# 2_Microcontroler_48.net
KiCad netlist of a schematic drawn in Altium Designer
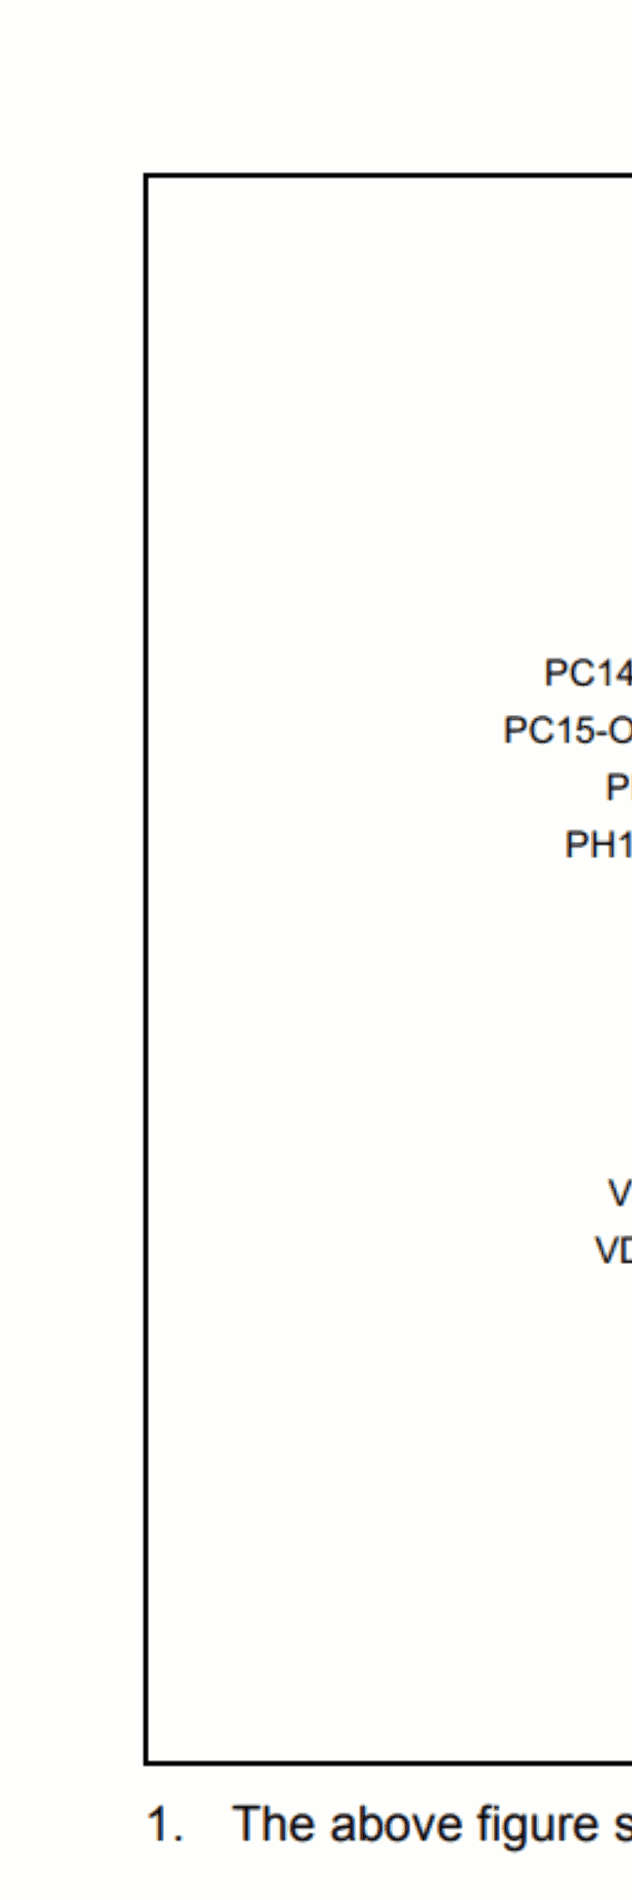
[diagram p0: 2_Microcontroler_48.SchDoc, top left]
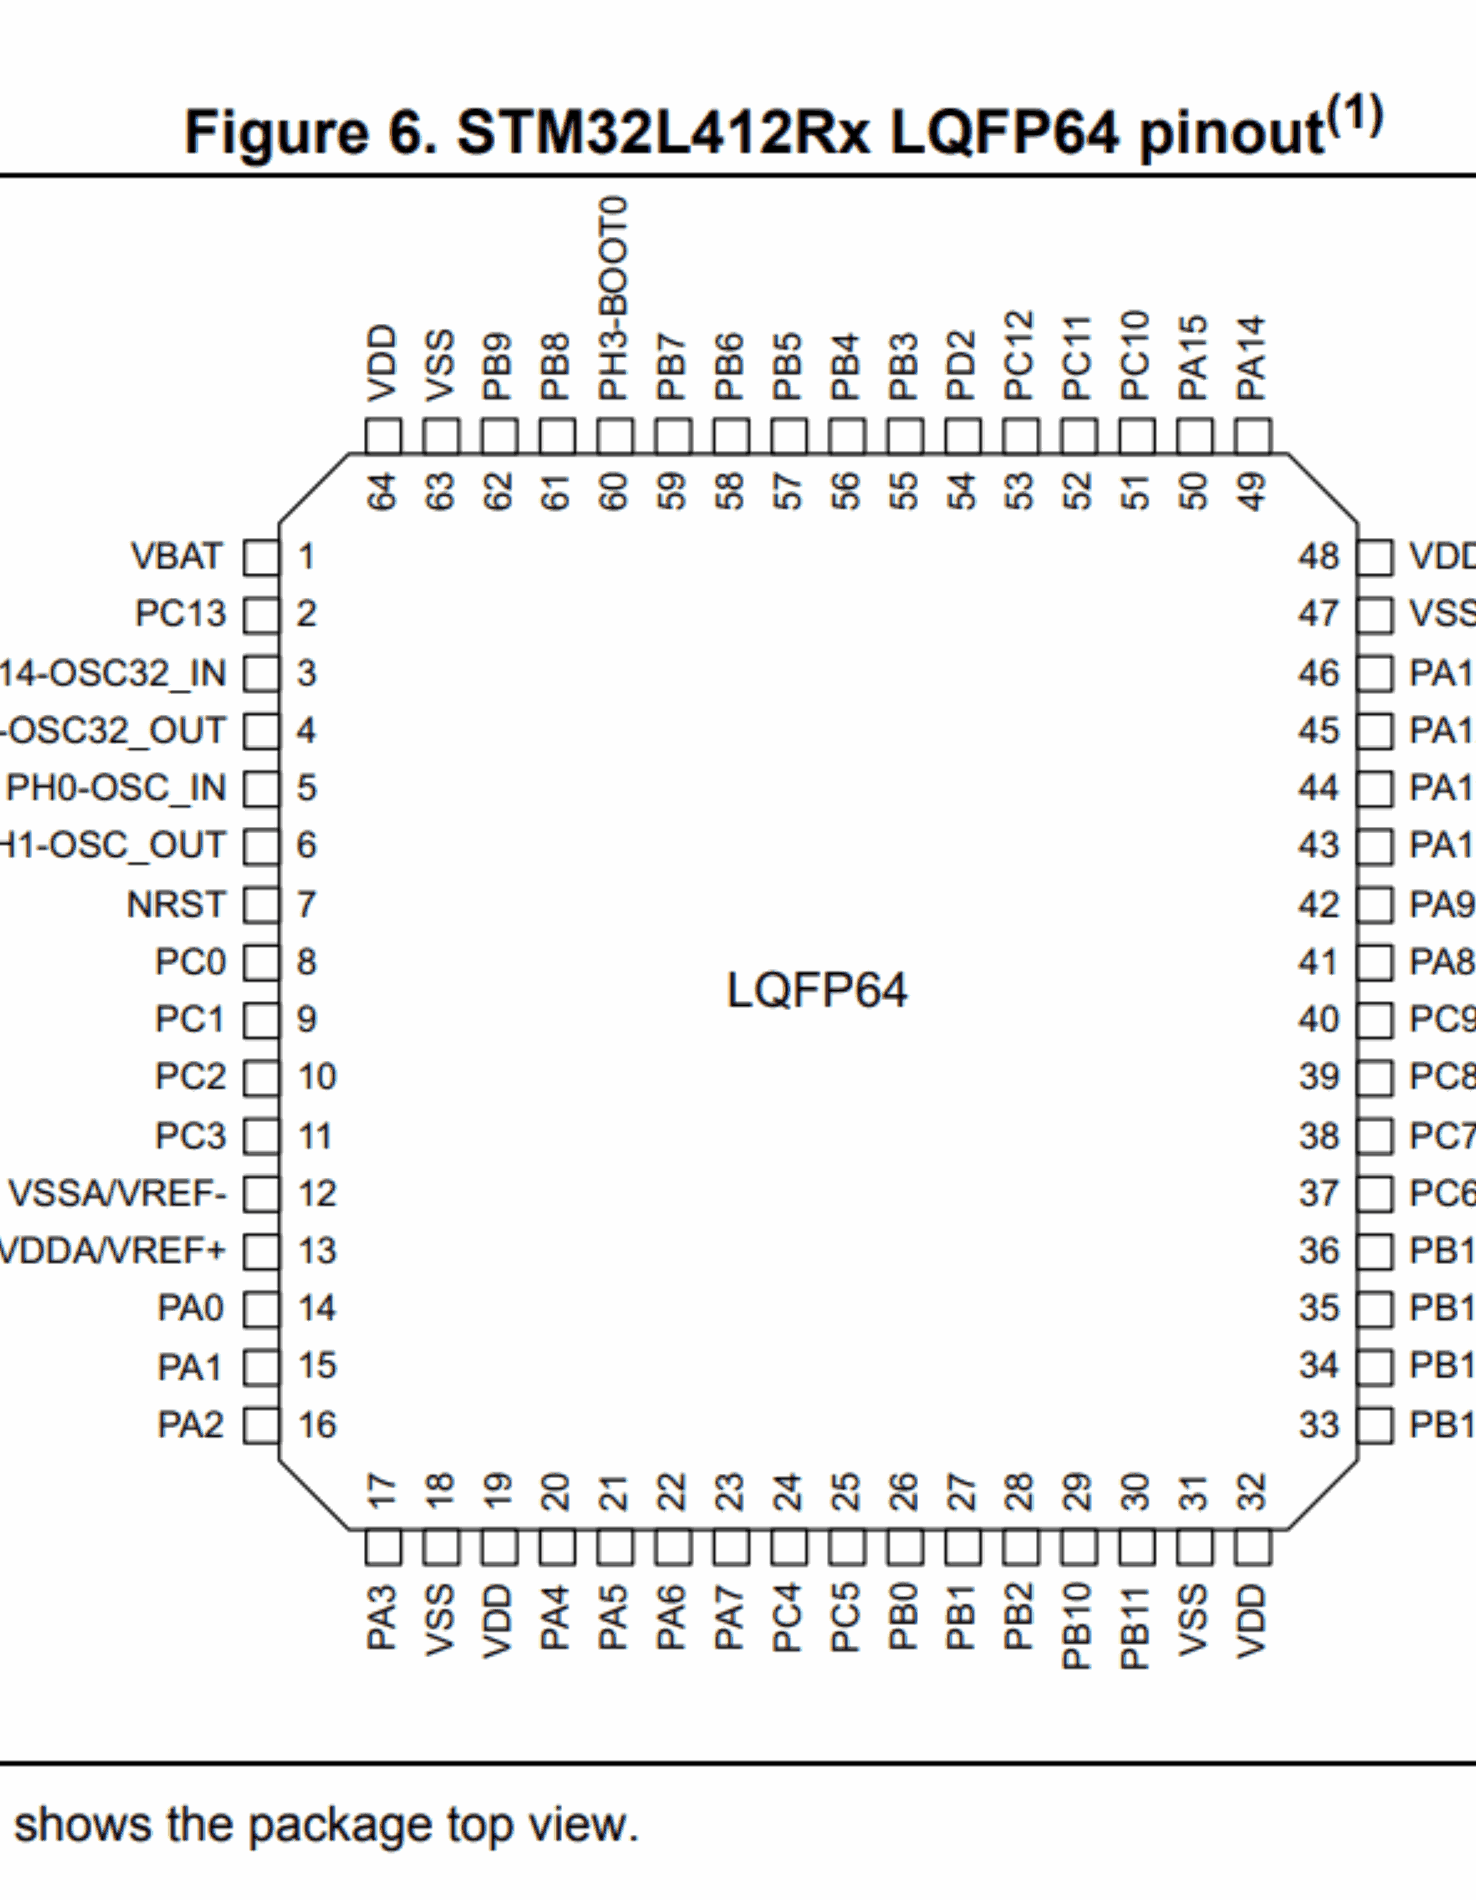
[diagram p1: 2_Microcontroler_48.SchDoc, top middle]
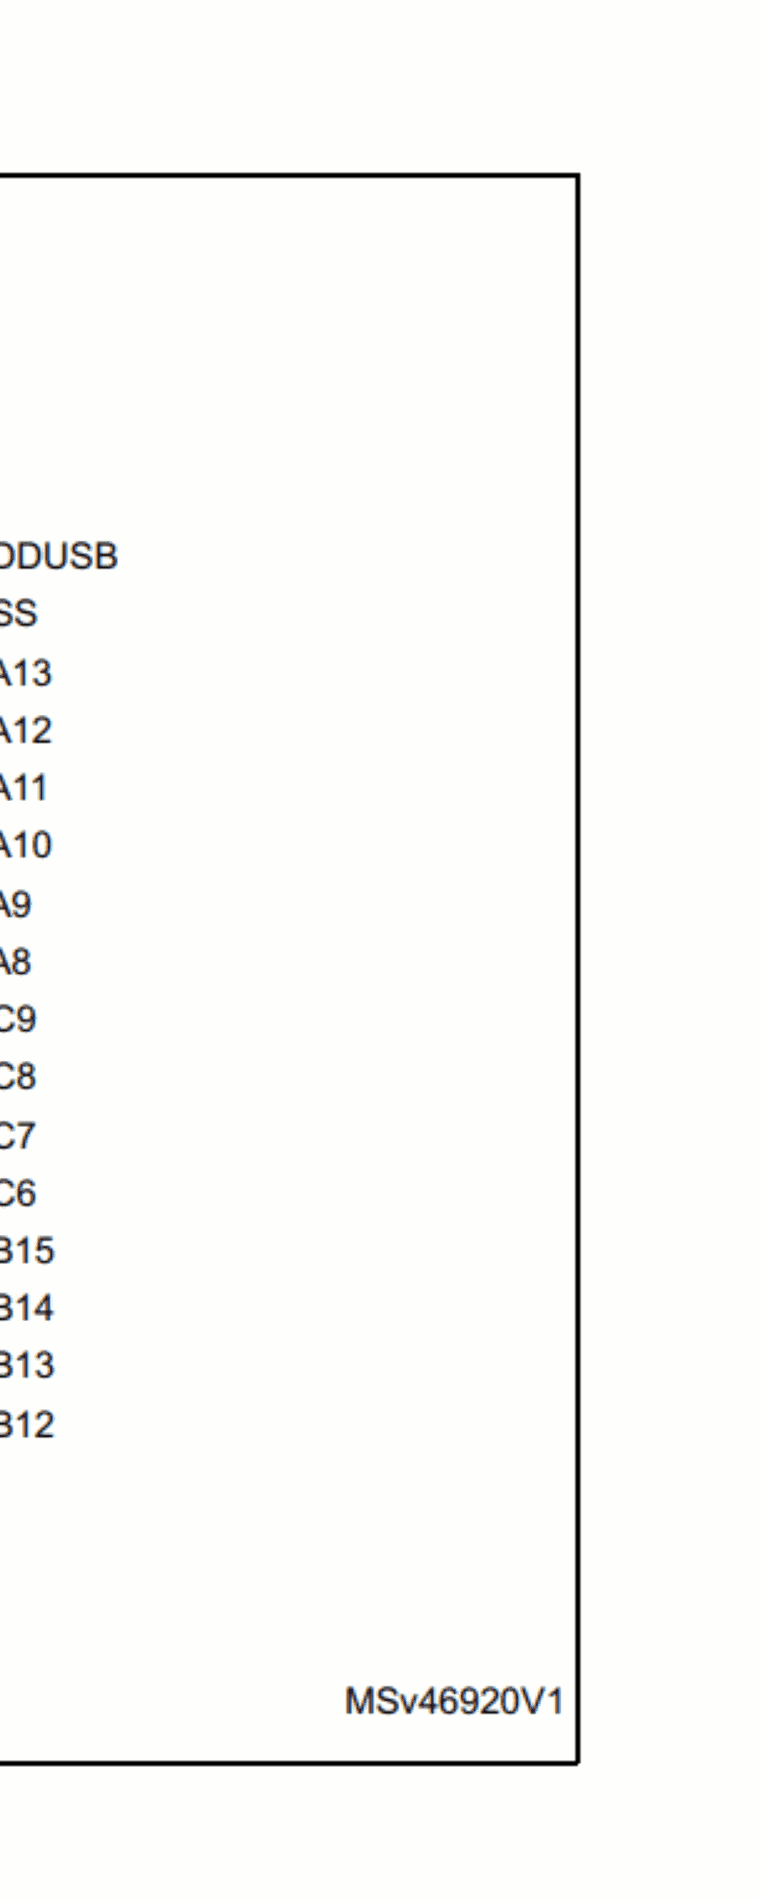
[diagram p2: 2_Microcontroler_48.SchDoc, top right]
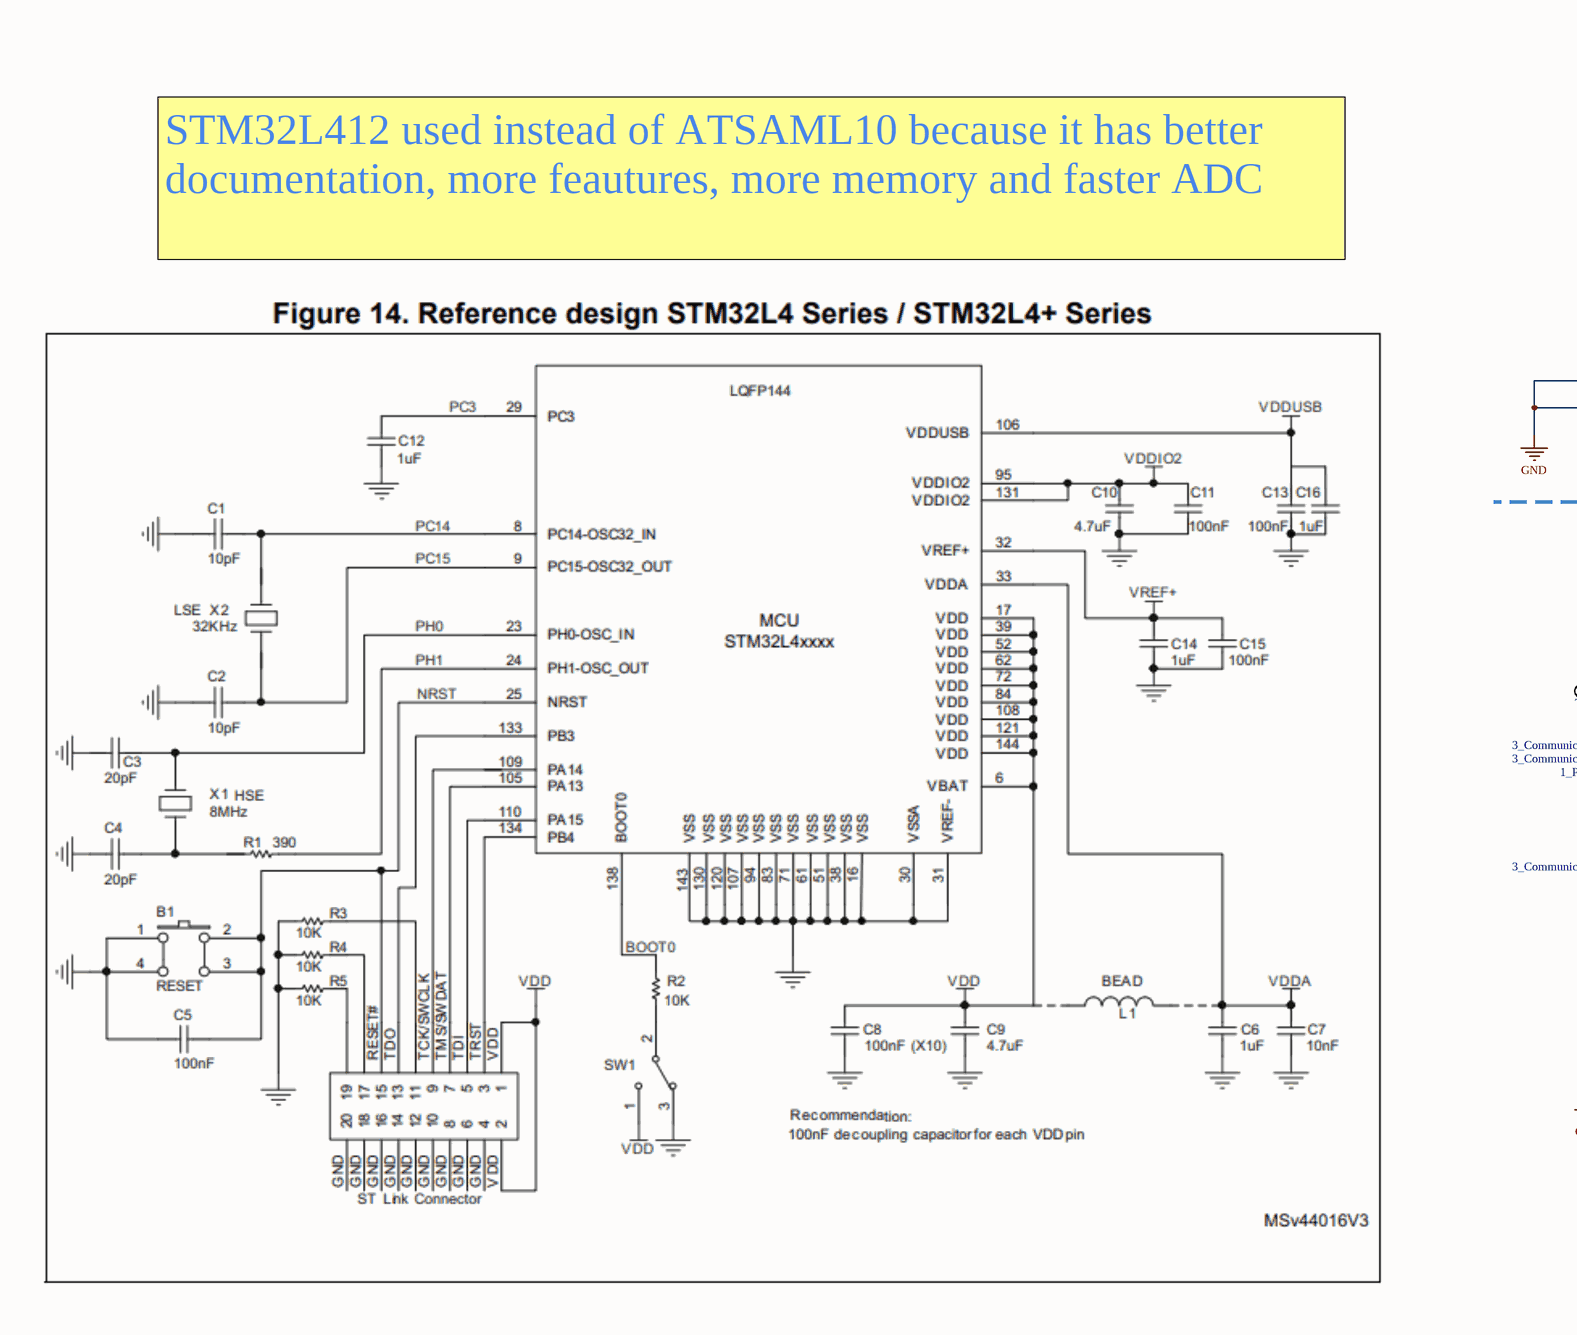
[diagram p3: 2_Microcontroler_48.SchDoc, bottom left]
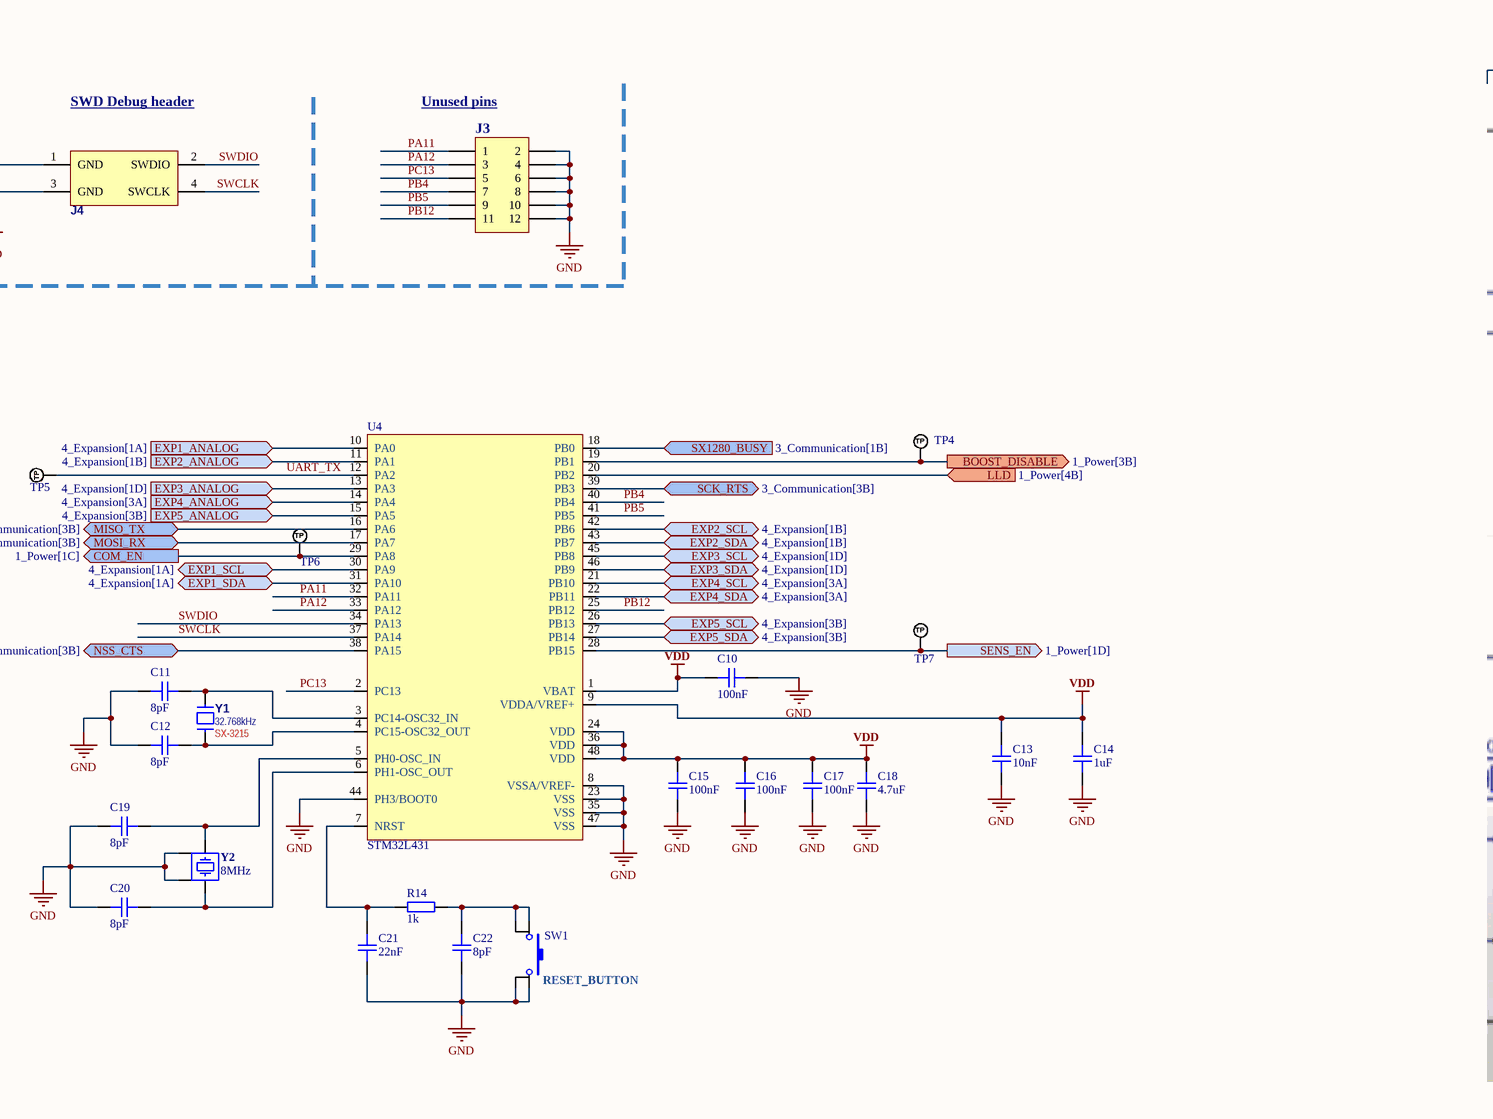
[diagram p4: 2_Microcontroler_48.SchDoc, bottom middle]
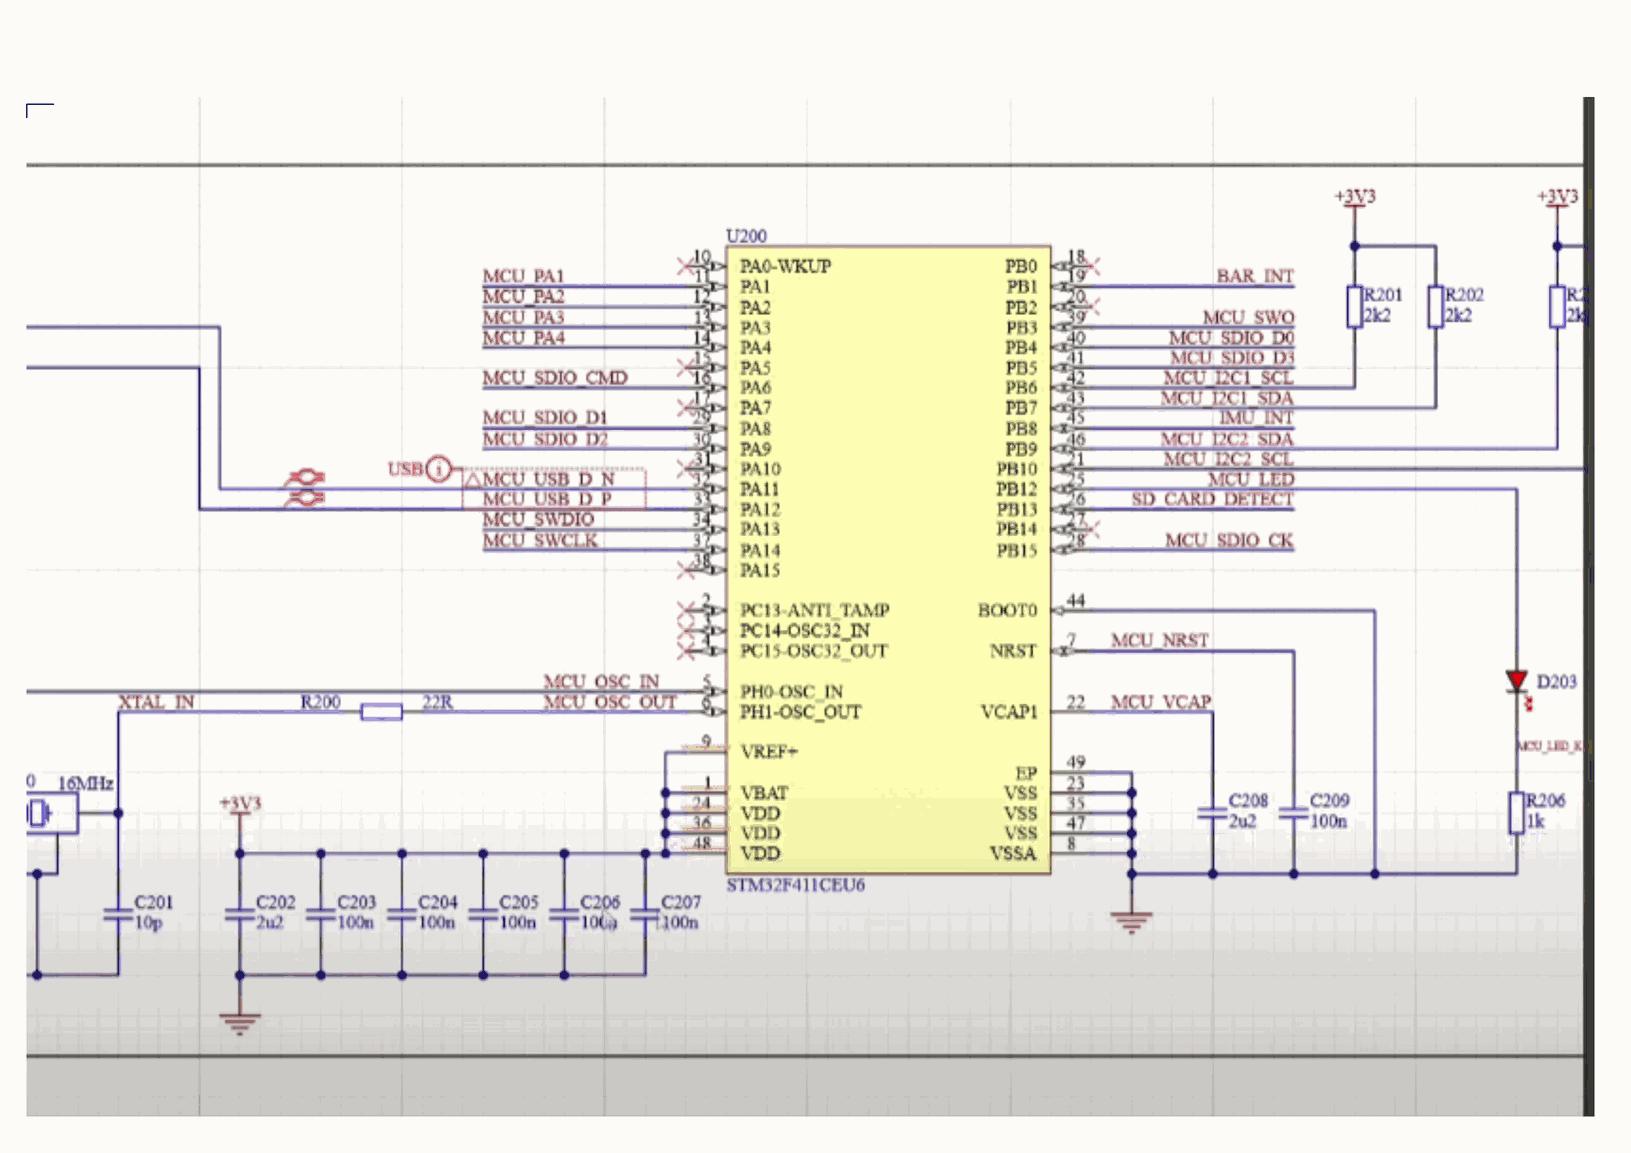
[diagram p5: 2_Microcontroler_48.SchDoc, bottom right]

(export (version "E")
  (design (tool "Eeschema 10.0.6"))
  (components
    (comp (ref "C10")
      (value "100nF")
      (footprint "C0603")
      (description "Capacitor SMD 0603")
      (libsource (lib "Schlib_H2") (part "CAP_0603"))
    )
    (comp (ref "C11")
      (value "8pF")
      (footprint "C0603")
      (description "Capacitor SMD 0603")
      (libsource (lib "Schlib_H2") (part "CAP_0603"))
    )
    (comp (ref "C12")
      (value "8pF")
      (footprint "C0603")
      (description "Capacitor SMD 0603")
      (libsource (lib "Schlib_H2") (part "CAP_0603"))
    )
    (comp (ref "C13")
      (value "10nF")
      (footprint "C0603")
      (description "Capacitor SMD 0603")
      (libsource (lib "Schlib_H2") (part "CAP_0603"))
    )
    (comp (ref "C14")
      (value "1uF")
      (footprint "C0603")
      (description "Capacitor SMD 0603")
      (libsource (lib "Schlib_H2") (part "CAP_0603"))
    )
    (comp (ref "C15")
      (value "100nF")
      (footprint "C0603")
      (description "Capacitor SMD 0603")
      (libsource (lib "Schlib_H2") (part "CAP_0603"))
    )
    (comp (ref "C16")
      (value "100nF")
      (footprint "C0603")
      (description "Capacitor SMD 0603")
      (libsource (lib "Schlib_H2") (part "CAP_0603"))
    )
    (comp (ref "C17")
      (value "100nF")
      (footprint "C0603")
      (description "Capacitor SMD 0603")
      (libsource (lib "Schlib_H2") (part "CAP_0603"))
    )
    (comp (ref "C18")
      (value "4.7uF")
      (footprint "C0603")
      (description "Capacitor SMD 0603")
      (libsource (lib "Schlib_H2") (part "CAP_0603"))
    )
    (comp (ref "C19")
      (value "8pF")
      (footprint "C0603")
      (description "Capacitor SMD 0603")
      (libsource (lib "Schlib_H2") (part "CAP_0603"))
    )
    (comp (ref "C20")
      (value "8pF")
      (footprint "C0603")
      (description "Capacitor SMD 0603")
      (libsource (lib "Schlib_H2") (part "CAP_0603"))
    )
    (comp (ref "C21")
      (value "22nF")
      (footprint "C0603")
      (description "Capacitor SMD 0603")
      (libsource (lib "Schlib_H2") (part "CAP_0603"))
    )
    (comp (ref "C22")
      (value "8pF")
      (footprint "C0603")
      (description "Capacitor SMD 0603")
      (libsource (lib "Schlib_H2") (part "CAP_0603"))
    )
    (comp (ref "J3")
      (value "Header 6X2")
      (footprint "HEADER_6x2_2.54")
      (description "Header, 12-Pin, Dual row")
      (fields (field (name "PUBLISHER") "Altium Limited"))
      (libsource (lib "Schlib_H2") (part "Header 6x2"))
    )
    (comp (ref "J4")
      (value "SWD connector")
      (footprint "HEADER_2x2_2.54")
      (description "Single Wire Debug connector with UART _TX pin")
      (libsource (lib "Schlib_H2") (part "SWD connector"))
    )
    (comp (ref "R14")
      (value "1k")
      (footprint "R0603")
      (description "Resistor SMD 0603")
      (libsource (lib "Schlib_H2") (part "RES_0603"))
    )
    (comp (ref "SW1")
      (value "PTS645SM43SMTR92 LFS")
      (footprint "SW_SKRPACE010")
      (description "Switch")
      (fields (field (name "PUBLISHER") "Altium Limited"))
      (libsource (lib "Schlib_H2") (part "SW-PB"))
    )
    (comp (ref "TP4")
      (value "TP_NOBOM")
      (footprint "TEST_PAD_THD")
      (description "Test Point Round 1mm (NO BOM)")
      (libsource (lib "Schlib_H2") (part "TEST_POINT_RND_1MM"))
    )
    (comp (ref "TP5")
      (value "TP_NOBOM")
      (footprint "TEST_PAD_THD")
      (description "Test Point Round 1mm (NO BOM)")
      (libsource (lib "Schlib_H2") (part "TEST_POINT_RND_1MM"))
    )
    (comp (ref "TP6")
      (value "TP_NOBOM")
      (footprint "TEST_PAD_THD")
      (description "Test Point Round 1mm (NO BOM)")
      (libsource (lib "Schlib_H2") (part "TEST_POINT_RND_1MM"))
    )
    (comp (ref "TP7")
      (value "TP_NOBOM")
      (footprint "TEST_PAD_THD")
      (description "Test Point Round 1mm (NO BOM)")
      (libsource (lib "Schlib_H2") (part "TEST_POINT_RND_1MM"))
    )
    (comp (ref "U4")
      (value "STM32L431")
      (footprint "QFPN-48")
      (description "Ultra-low-power Arm® Cortex®-M4 32-bit MCU+FPU, 100DMIPS,\r\n up to 128KB flash, 40KB SRAM(LQFP48)")
      (libsource (lib "Schlib_H2") (part "STM32L431"))
    )
    (comp (ref "Y1")
      (value "32.768kHz")
      (footprint "CRYSTAL_SX-3215")
      (description "Crystal")
      (fields (field (name "PACKAGEREFERENCE") "SX-3215"))
      (libsource (lib "Schlib_H2") (part "CRYSTAL_1"))
    )
    (comp (ref "Y2")
      (value "8MHz")
      (footprint "CRYSTAL_ECX-32_3.2x2.5x0.8 - duplicate")
      (description "Crystal")
      (fields
        (field (name "MANUFACTURER") "Epson")
        (field (name "MANUFACTURER PART NUMBER") "TSX-3225 24.0000MF15X-AC")
      )
      (libsource (lib "Schlib_H2") (part "Crystal"))
    )
  )
  (nets
    (net (code "1") (name "/BOOST_DISABLE") (class "Default")
      (node (ref "TP4") (pin "1") (pinfunction "TP_1") (pintype "passive"))
      (node (ref "U4") (pin "19") (pinfunction "PB1_19") (pintype "passive"))
    )
    (net (code "2") (name "/COM_EN") (class "Default")
      (node (ref "TP6") (pin "1") (pinfunction "TP_1") (pintype "passive"))
      (node (ref "U4") (pin "29") (pinfunction "PA8_29") (pintype "passive"))
    )
    (net (code "3") (name "/EXP1_ANALOG") (class "Default")
      (node (ref "U4") (pin "10") (pinfunction "PA0_10") (pintype "passive"))
    )
    (net (code "4") (name "/EXP1_SCL") (class "Default")
      (node (ref "U4") (pin "30") (pinfunction "PA9_30") (pintype "passive"))
    )
    (net (code "5") (name "/EXP1_SDA") (class "Default")
      (node (ref "U4") (pin "31") (pinfunction "PA10_31") (pintype "passive"))
    )
    (net (code "6") (name "/EXP2_ANALOG") (class "Default")
      (node (ref "U4") (pin "11") (pinfunction "PA1_11") (pintype "passive"))
    )
    (net (code "7") (name "/EXP2_SCL") (class "Default")
      (node (ref "U4") (pin "42") (pinfunction "PB6_42") (pintype "passive"))
    )
    (net (code "8") (name "/EXP2_SDA") (class "Default")
      (node (ref "U4") (pin "43") (pinfunction "PB7_43") (pintype "passive"))
    )
    (net (code "9") (name "/EXP3_ANALOG") (class "Default")
      (node (ref "U4") (pin "13") (pinfunction "PA3_13") (pintype "passive"))
    )
    (net (code "10") (name "/EXP3_SCL") (class "Default")
      (node (ref "U4") (pin "45") (pinfunction "PB8_45") (pintype "passive"))
    )
    (net (code "11") (name "/EXP3_SDA") (class "Default")
      (node (ref "U4") (pin "46") (pinfunction "PB9_46") (pintype "passive"))
    )
    (net (code "12") (name "/EXP4_ANALOG") (class "Default")
      (node (ref "U4") (pin "14") (pinfunction "PA4_14") (pintype "passive"))
    )
    (net (code "13") (name "/EXP4_SCL") (class "Default")
      (node (ref "U4") (pin "21") (pinfunction "PB10_21") (pintype "passive"))
    )
    (net (code "14") (name "/EXP4_SDA") (class "Default")
      (node (ref "U4") (pin "22") (pinfunction "PB11_22") (pintype "passive"))
    )
    (net (code "15") (name "/EXP5_ANALOG") (class "Default")
      (node (ref "U4") (pin "15") (pinfunction "PA5_15") (pintype "passive"))
    )
    (net (code "16") (name "/EXP5_SCL") (class "Default")
      (node (ref "U4") (pin "26") (pinfunction "PB13_26") (pintype "passive"))
    )
    (net (code "17") (name "/EXP5_SDA") (class "Default")
      (node (ref "U4") (pin "27") (pinfunction "PB14_27") (pintype "passive"))
    )
    (net (code "18") (name "/LLD") (class "Default")
      (node (ref "U4") (pin "20") (pinfunction "PB2_20") (pintype "passive"))
    )
    (net (code "19") (name "/MISO_TX") (class "Default")
      (node (ref "U4") (pin "16") (pinfunction "PA6_16") (pintype "passive"))
    )
    (net (code "20") (name "/MOSI_RX") (class "Default")
      (node (ref "U4") (pin "17") (pinfunction "PA7_17") (pintype "passive"))
    )
    (net (code "21") (name "/NSS_CTS") (class "Default")
      (node (ref "U4") (pin "38") (pinfunction "PA15_38") (pintype "passive"))
    )
    (net (code "22") (name "/PA11") (class "Default")
      (node (ref "J3") (pin "1") (pinfunction "1_1") (pintype "passive"))
      (node (ref "U4") (pin "32") (pinfunction "PA11_32") (pintype "passive"))
    )
    (net (code "23") (name "/PA12") (class "Default")
      (node (ref "J3") (pin "3") (pinfunction "3_3") (pintype "passive"))
      (node (ref "U4") (pin "33") (pinfunction "PA12_33") (pintype "passive"))
    )
    (net (code "24") (name "/PB4") (class "Default")
      (node (ref "J3") (pin "7") (pinfunction "7_7") (pintype "passive"))
      (node (ref "U4") (pin "40") (pinfunction "PB4_40") (pintype "passive"))
    )
    (net (code "25") (name "/PB5") (class "Default")
      (node (ref "J3") (pin "9") (pinfunction "9_9") (pintype "passive"))
      (node (ref "U4") (pin "41") (pinfunction "PB5_41") (pintype "passive"))
    )
    (net (code "26") (name "/PB12") (class "Default")
      (node (ref "J3") (pin "11") (pinfunction "11_11") (pintype "passive"))
      (node (ref "U4") (pin "25") (pinfunction "PB12_25") (pintype "passive"))
    )
    (net (code "27") (name "/PC13") (class "Default")
      (node (ref "J3") (pin "5") (pinfunction "5_5") (pintype "passive"))
      (node (ref "U4") (pin "2") (pinfunction "PC13_2") (pintype "passive"))
    )
    (net (code "28") (name "/SCK_RTS") (class "Default")
      (node (ref "U4") (pin "39") (pinfunction "PB3_39") (pintype "passive"))
    )
    (net (code "29") (name "/SENS_EN") (class "Default")
      (node (ref "TP7") (pin "1") (pinfunction "TP_1") (pintype "passive"))
      (node (ref "U4") (pin "28") (pinfunction "PB15_28") (pintype "passive"))
    )
    (net (code "30") (name "/SWCLK") (class "Default")
      (node (ref "J4") (pin "4") (pinfunction "SWCLK_4") (pintype "passive"))
      (node (ref "U4") (pin "37") (pinfunction "PA14_37") (pintype "passive"))
    )
    (net (code "31") (name "/SWDIO") (class "Default")
      (node (ref "J4") (pin "2") (pinfunction "SWDIO_2") (pintype "passive"))
      (node (ref "U4") (pin "34") (pinfunction "PA13_34") (pintype "passive"))
    )
    (net (code "32") (name "/SX1280_BUSY") (class "Default")
      (node (ref "U4") (pin "18") (pinfunction "PB0_18") (pintype "passive"))
    )
    (net (code "33") (name "/UART_TX") (class "Default")
      (node (ref "TP5") (pin "1") (pinfunction "TP_1") (pintype "passive"))
      (node (ref "U4") (pin "12") (pinfunction "PA2_12") (pintype "passive"))
    )
    (net (code "34") (name "GND") (class "Default")
      (node (ref "C10") (pin "1") (pinfunction "1_1") (pintype "passive"))
      (node (ref "C11") (pin "1") (pinfunction "1_1") (pintype "passive"))
      (node (ref "C12") (pin "1") (pinfunction "1_1") (pintype "passive"))
      (node (ref "C13") (pin "1") (pinfunction "1_1") (pintype "passive"))
      (node (ref "C14") (pin "1") (pinfunction "1_1") (pintype "passive"))
      (node (ref "C15") (pin "1") (pinfunction "1_1") (pintype "passive"))
      (node (ref "C16") (pin "1") (pinfunction "1_1") (pintype "passive"))
      (node (ref "C17") (pin "1") (pinfunction "1_1") (pintype "passive"))
      (node (ref "C18") (pin "1") (pinfunction "1_1") (pintype "passive"))
      (node (ref "C19") (pin "1") (pinfunction "1_1") (pintype "passive"))
      (node (ref "C20") (pin "1") (pinfunction "1_1") (pintype "passive"))
      (node (ref "C21") (pin "1") (pinfunction "1_1") (pintype "passive"))
      (node (ref "C22") (pin "1") (pinfunction "1_1") (pintype "passive"))
      (node (ref "J3") (pin "10") (pinfunction "10_10") (pintype "passive"))
      (node (ref "J3") (pin "12") (pinfunction "12_12") (pintype "passive"))
      (node (ref "J3") (pin "2") (pinfunction "2_2") (pintype "passive"))
      (node (ref "J3") (pin "4") (pinfunction "4_4") (pintype "passive"))
      (node (ref "J3") (pin "6") (pinfunction "6_6") (pintype "passive"))
      (node (ref "J3") (pin "8") (pinfunction "8_8") (pintype "passive"))
      (node (ref "J4") (pin "1") (pinfunction "GND_1") (pintype "passive"))
      (node (ref "J4") (pin "3") (pinfunction "GND_3") (pintype "passive"))
      (node (ref "SW1") (pin "3") (pinfunction "3_3") (pintype "passive"))
      (node (ref "SW1") (pin "4") (pinfunction "4_4") (pintype "passive"))
      (node (ref "U4") (pin "23") (pinfunction "VSS_23") (pintype "passive"))
      (node (ref "U4") (pin "35") (pinfunction "VSS_35") (pintype "passive"))
      (node (ref "U4") (pin "44") (pinfunction "PH3/BOOT0_44") (pintype "passive"))
      (node (ref "U4") (pin "47") (pinfunction "VSS_47") (pintype "passive"))
      (node (ref "U4") (pin "8") (pinfunction "VSSA/VREF-_8") (pintype "passive"))
      (node (ref "Y2") (pin "2") (pinfunction "2_2") (pintype "passive"))
      (node (ref "Y2") (pin "4") (pinfunction "4_4") (pintype "passive"))
    )
    (net (code "35") (name "Net-(C22-Pad2)") (class "Default")
      (node (ref "C22") (pin "2") (pinfunction "2_2") (pintype "passive"))
      (node (ref "R14") (pin "2") (pinfunction "2_2") (pintype "passive"))
      (node (ref "SW1") (pin "1") (pinfunction "1_1") (pintype "passive"))
      (node (ref "SW1") (pin "2") (pinfunction "2_2") (pintype "passive"))
    )
    (net (code "36") (name "Net-(U4-NRST)") (class "Default")
      (node (ref "C21") (pin "2") (pinfunction "2_2") (pintype "passive"))
      (node (ref "R14") (pin "1") (pinfunction "1_1") (pintype "passive"))
      (node (ref "U4") (pin "7") (pinfunction "NRST_7") (pintype "passive"))
    )
    (net (code "37") (name "Net-(U4-PC14-OSC32_IN)") (class "Default")
      (node (ref "C11") (pin "2") (pinfunction "2_2") (pintype "passive"))
      (node (ref "U4") (pin "3") (pinfunction "PC14-OSC32_IN_3") (pintype "passive"))
      (node (ref "Y1") (pin "2") (pinfunction "2_2") (pintype "passive"))
    )
    (net (code "38") (name "Net-(U4-PC15-OSC32_OUT)") (class "Default")
      (node (ref "C12") (pin "2") (pinfunction "2_2") (pintype "passive"))
      (node (ref "U4") (pin "4") (pinfunction "PC15-OSC32_OUT_4") (pintype "passive"))
      (node (ref "Y1") (pin "1") (pinfunction "1_1") (pintype "passive"))
    )
    (net (code "39") (name "Net-(U4-PH0-OSC_IN)") (class "Default")
      (node (ref "C19") (pin "2") (pinfunction "2_2") (pintype "passive"))
      (node (ref "U4") (pin "5") (pinfunction "PH0-OSC_IN_5") (pintype "passive"))
      (node (ref "Y2") (pin "3") (pinfunction "3_3") (pintype "passive"))
    )
    (net (code "40") (name "Net-(U4-PH1-OSC_OUT)") (class "Default")
      (node (ref "C20") (pin "2") (pinfunction "2_2") (pintype "passive"))
      (node (ref "U4") (pin "6") (pinfunction "PH1-OSC_OUT_6") (pintype "passive"))
      (node (ref "Y2") (pin "1") (pinfunction "1_1") (pintype "passive"))
    )
    (net (code "41") (name "VDD") (class "Default")
      (node (ref "C10") (pin "2") (pinfunction "2_2") (pintype "passive"))
      (node (ref "C13") (pin "2") (pinfunction "2_2") (pintype "passive"))
      (node (ref "C14") (pin "2") (pinfunction "2_2") (pintype "passive"))
      (node (ref "C15") (pin "2") (pinfunction "2_2") (pintype "passive"))
      (node (ref "C16") (pin "2") (pinfunction "2_2") (pintype "passive"))
      (node (ref "C17") (pin "2") (pinfunction "2_2") (pintype "passive"))
      (node (ref "C18") (pin "2") (pinfunction "2_2") (pintype "passive"))
      (node (ref "U4") (pin "1") (pinfunction "VBAT_1") (pintype "passive"))
      (node (ref "U4") (pin "24") (pinfunction "VDD_24") (pintype "passive"))
      (node (ref "U4") (pin "36") (pinfunction "VDD_36") (pintype "passive"))
      (node (ref "U4") (pin "48") (pinfunction "VDD_48") (pintype "passive"))
      (node (ref "U4") (pin "9") (pinfunction "VDDA/VREF+_9") (pintype "passive"))
    )
  )
)
